# mpg-200-prototype_v3-with-logo.net
KiCad netlist of a schematic drawn in EAGLE
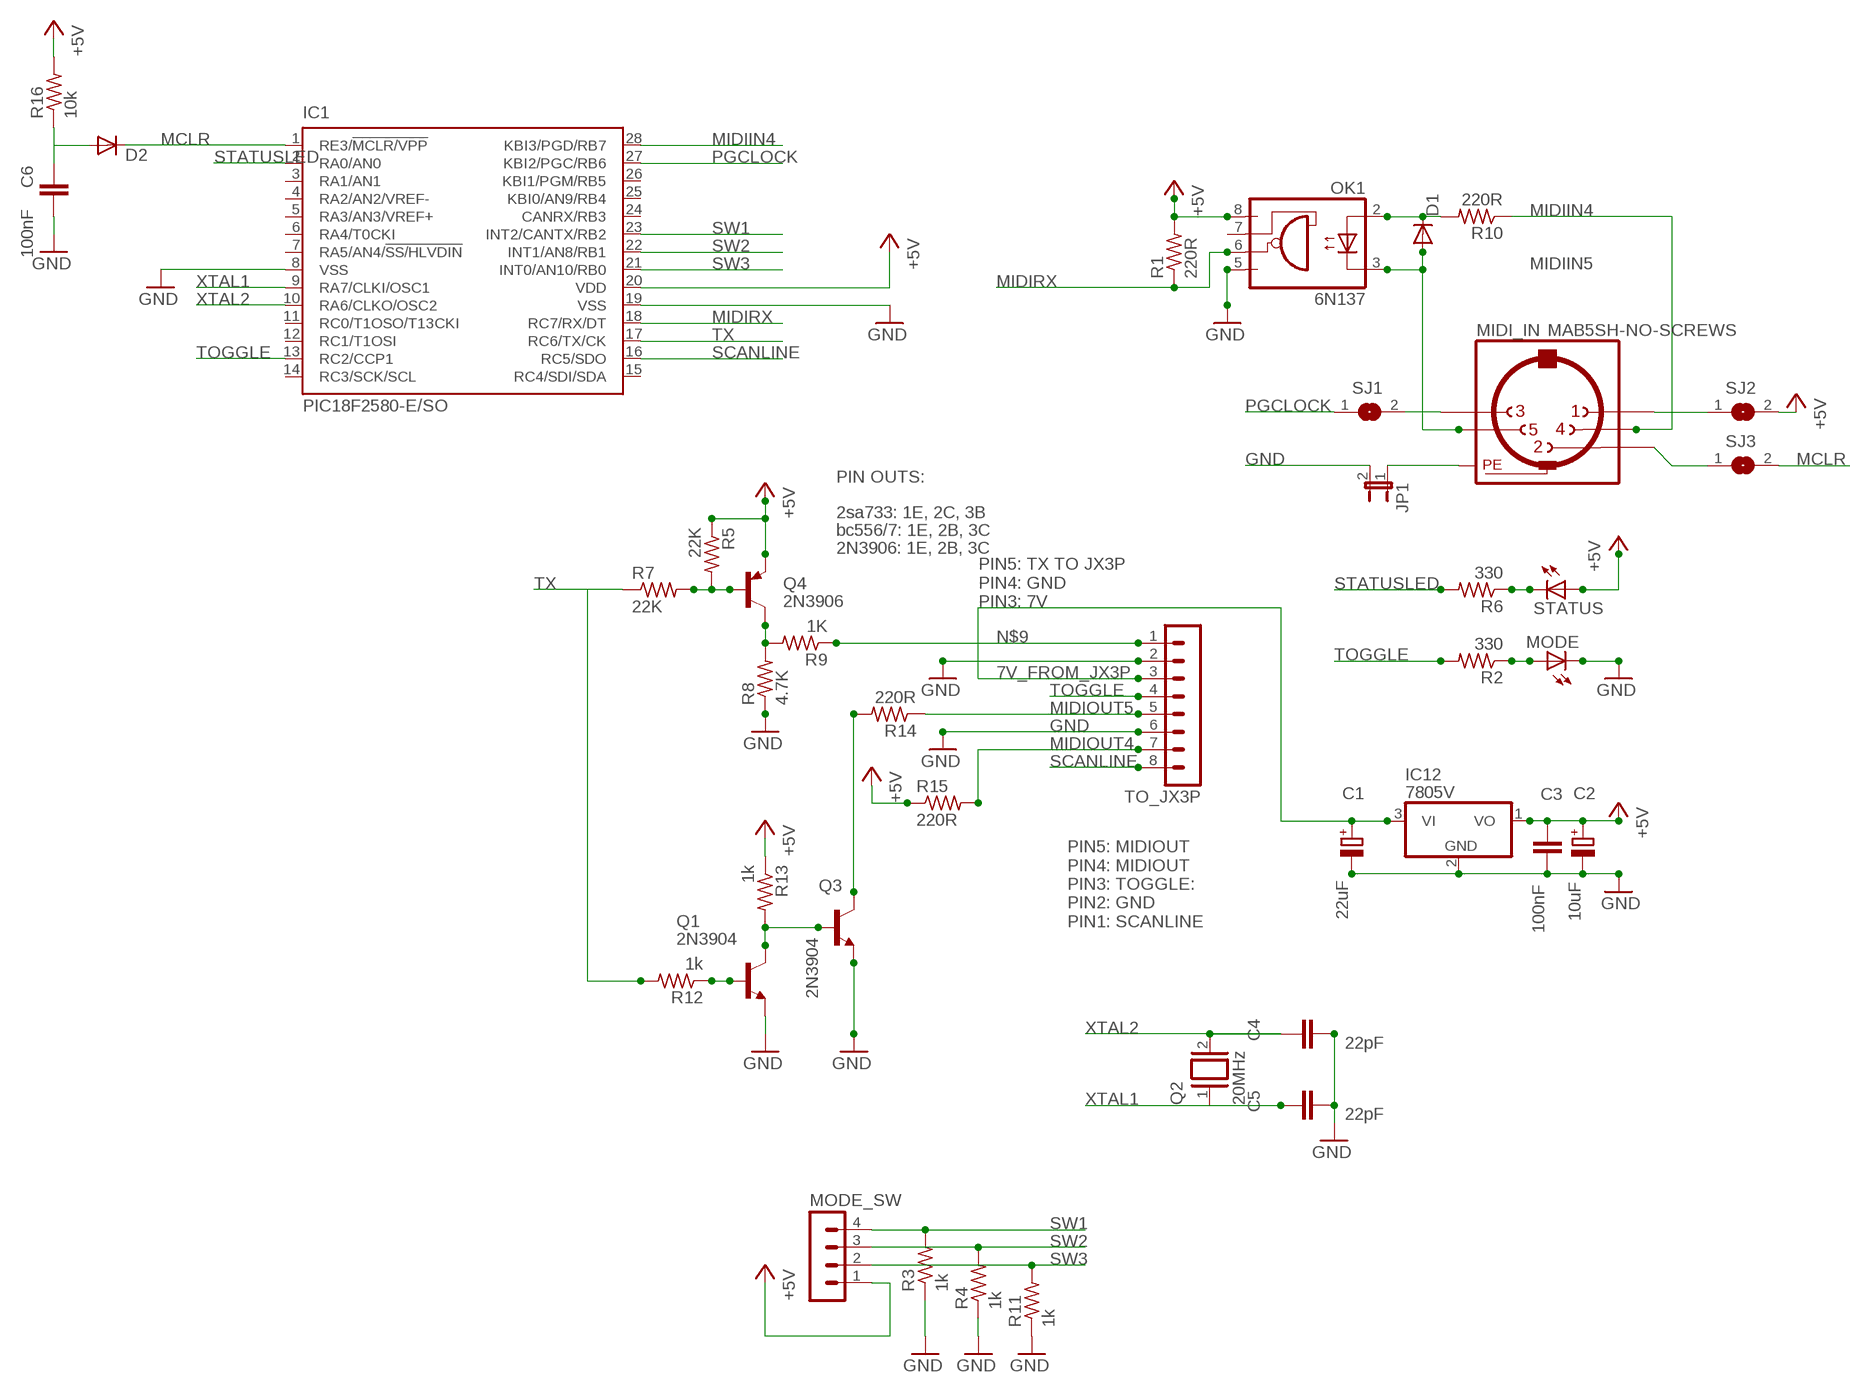
[diagram p0: schematic, sheet 1]

(export (version "E")
  (design (tool "Eeschema 10.0.6"))
  (components
    (comp (ref "C1")
      (value "22uF")
      (footprint "eagle-import:E2,5-5")
      (libsource (lib "eagle-import") (part "CPOL-EUE2.5-5"))
    )
    (comp (ref "C2")
      (value "10uF")
      (footprint "eagle-import:E2,5-5")
      (libsource (lib "eagle-import") (part "CPOL-EUE2.5-5"))
    )
    (comp (ref "C3")
      (value "100nF")
      (footprint "eagle-import:C0805")
      (libsource (lib "eagle-import") (part "C-EUC0805"))
    )
    (comp (ref "C4")
      (value "22pF")
      (footprint "eagle-import:C0805")
      (libsource (lib "eagle-import") (part "C-EUC0805"))
    )
    (comp (ref "C5")
      (value "22pF")
      (footprint "eagle-import:C0805")
      (libsource (lib "eagle-import") (part "C-EUC0805"))
    )
    (comp (ref "C6")
      (value "100nF")
      (footprint "eagle-import:C0805")
      (libsource (lib "eagle-import") (part "C-EUC0805"))
    )
    (comp (ref "D1")
      (value "DIODE-SOD80C")
      (footprint "eagle-import:SOD80C")
      (libsource (lib "eagle-import") (part "DIODE-SOD80C"))
    )
    (comp (ref "D2")
      (value "DIODE-SOD80C")
      (footprint "eagle-import:SOD80C")
      (libsource (lib "eagle-import") (part "DIODE-SOD80C"))
    )
    (comp (ref "IC1")
      (value "PIC18F2580-E/SO")
      (footprint "eagle-import:SO28W")
      (fields (field (name "MF") "MICROCHIP") (field (name "MPN") "PIC18F2580-I/SO"))
      (libsource (lib "eagle-import") (part "PIC18F280-E/SO5"))
    )
    (comp (ref "IC12")
      (value "7805V")
      (footprint "eagle-import:TO92")
      (libsource (lib "eagle-import") (part "78L05"))
    )
    (comp (ref "JP1")
      (value "JP1E")
      (footprint "eagle-import:JP1")
      (libsource (lib "eagle-import") (part "JP1E"))
    )
    (comp (ref "MIDI_IN")
      (value "MAB5SH-NO-SCREWS")
      (footprint "eagle-import:MAB5SH-NO-SCREWS")
      (libsource (lib "eagle-import") (part "MAB5SH-NO-SCREWS"))
    )
    (comp (ref "MODE")
      (value "LED3MM")
      (footprint "eagle-import:LED3MM")
      (libsource (lib "eagle-import") (part "LED3MM"))
    )
    (comp (ref "MODE_SW")
      (value "MA04-1")
      (footprint "eagle-import:MA04-1")
      (libsource (lib "eagle-import") (part "MA04-1"))
    )
    (comp (ref "OK1")
      (value "6N137")
      (footprint "eagle-import:DIL08")
      (libsource (lib "eagle-import") (part "6N137"))
    )
    (comp (ref "Q1")
      (value "2N3904")
      (footprint "eagle-import:TO92")
      (libsource (lib "eagle-import") (part "2N3904"))
    )
    (comp (ref "Q2")
      (value "20MHz")
      (footprint "eagle-import:QS")
      (libsource (lib "eagle-import") (part "XTAL/S"))
    )
    (comp (ref "Q3")
      (value "2N3904")
      (footprint "eagle-import:TO92")
      (libsource (lib "eagle-import") (part "2N3904"))
    )
    (comp (ref "Q4")
      (value "2N3906")
      (footprint "eagle-import:TO92")
      (libsource (lib "eagle-import") (part "2N3906"))
    )
    (comp (ref "R1")
      (value "220R")
      (footprint "eagle-import:R0805")
      (libsource (lib "eagle-import") (part "R-US_R0805"))
    )
    (comp (ref "R2")
      (value "330")
      (footprint "eagle-import:R0805")
      (libsource (lib "eagle-import") (part "R-US_R0805"))
    )
    (comp (ref "R3")
      (value "1k")
      (footprint "eagle-import:R0805")
      (libsource (lib "eagle-import") (part "R-US_R0805"))
    )
    (comp (ref "R4")
      (value "1k")
      (footprint "eagle-import:R0805")
      (libsource (lib "eagle-import") (part "R-US_R0805"))
    )
    (comp (ref "R5")
      (value "22K")
      (footprint "eagle-import:R0805")
      (libsource (lib "eagle-import") (part "R-US_R0805"))
    )
    (comp (ref "R6")
      (value "330")
      (footprint "eagle-import:R0805")
      (libsource (lib "eagle-import") (part "R-US_R0805"))
    )
    (comp (ref "R7")
      (value "22K")
      (footprint "eagle-import:R0805")
      (libsource (lib "eagle-import") (part "R-US_R0805"))
    )
    (comp (ref "R8")
      (value "4.7K")
      (footprint "eagle-import:R0805")
      (libsource (lib "eagle-import") (part "R-US_R0805"))
    )
    (comp (ref "R9")
      (value "1K")
      (footprint "eagle-import:R0805")
      (libsource (lib "eagle-import") (part "R-US_R0805"))
    )
    (comp (ref "R10")
      (value "220R")
      (footprint "eagle-import:R0805")
      (libsource (lib "eagle-import") (part "R-US_R0805"))
    )
    (comp (ref "R11")
      (value "1k")
      (footprint "eagle-import:R0805")
      (libsource (lib "eagle-import") (part "R-US_R0805"))
    )
    (comp (ref "R12")
      (value "1k")
      (footprint "eagle-import:R0805")
      (libsource (lib "eagle-import") (part "R-US_R0805"))
    )
    (comp (ref "R13")
      (value "1k")
      (footprint "eagle-import:R0805")
      (libsource (lib "eagle-import") (part "R-US_R0805"))
    )
    (comp (ref "R14")
      (value "220R")
      (footprint "eagle-import:R0805")
      (libsource (lib "eagle-import") (part "R-US_R0805"))
    )
    (comp (ref "R15")
      (value "220R")
      (footprint "eagle-import:R0805")
      (libsource (lib "eagle-import") (part "R-US_R0805"))
    )
    (comp (ref "R16")
      (value "10k")
      (footprint "eagle-import:R0805")
      (libsource (lib "eagle-import") (part "R-US_R0805"))
    )
    (comp (ref "SJ1") (value "SJ") (footprint "eagle-import:SJ") (libsource (lib "eagle-import") (part "SJ")))
    (comp (ref "SJ2") (value "SJ") (footprint "eagle-import:SJ") (libsource (lib "eagle-import") (part "SJ")))
    (comp (ref "SJ3") (value "SJ") (footprint "eagle-import:SJ") (libsource (lib "eagle-import") (part "SJ")))
    (comp (ref "STATUS")
      (value "LED3MM")
      (footprint "eagle-import:LED3MM")
      (libsource (lib "eagle-import") (part "LED3MM"))
    )
    (comp (ref "TO_JX3P")
      (value "MA08-1")
      (footprint "eagle-import:MA08-1")
      (libsource (lib "eagle-import") (part "MA08-1"))
    )
  )
  (nets
    (net (code "1") (name "+5V") (class "Default")
      (node (ref "C2") (pin "+") (pinfunction "+_+") (pintype "passive"))
      (node (ref "C3") (pin "1") (pinfunction "1_1") (pintype "passive"))
      (node (ref "IC1") (pin "20") (pinfunction "VDD_20") (pintype "power_in"))
      (node (ref "IC12") (pin "1") (pinfunction "VO_1") (pintype "passive"))
      (node (ref "MODE_SW") (pin "1") (pinfunction "1_1") (pintype "passive"))
      (node (ref "OK1") (pin "8") (pinfunction "VCC_8") (pintype "passive"))
      (node (ref "Q4") (pin "1") (pinfunction "E_1") (pintype "passive"))
      (node (ref "R1") (pin "2") (pinfunction "2_2") (pintype "passive"))
      (node (ref "R13") (pin "1") (pinfunction "1_1") (pintype "passive"))
      (node (ref "R15") (pin "1") (pinfunction "1_1") (pintype "passive"))
      (node (ref "R16") (pin "2") (pinfunction "2_2") (pintype "passive"))
      (node (ref "R5") (pin "1") (pinfunction "1_1") (pintype "passive"))
      (node (ref "SJ2") (pin "2") (pinfunction "2_2") (pintype "passive"))
      (node (ref "STATUS") (pin "A") (pinfunction "A_A") (pintype "passive"))
    )
    (net (code "2") (name "/7V_FROM_JX3P") (class "Default")
      (node (ref "C1") (pin "+") (pinfunction "+_+") (pintype "passive"))
      (node (ref "IC12") (pin "3") (pinfunction "VI_3") (pintype "input"))
      (node (ref "TO_JX3P") (pin "3") (pinfunction "3_3") (pintype "passive"))
    )
    (net (code "3") (name "/MCLR") (class "Default")
      (node (ref "D2") (pin "C") (pinfunction "C_C") (pintype "passive"))
      (node (ref "IC1") (pin "1") (pinfunction "RE3/~{MCLR/VPP}_1") (pintype "input"))
      (node (ref "SJ3") (pin "2") (pinfunction "2_2") (pintype "passive"))
    )
    (net (code "4") (name "/MIDIIN4") (class "Default")
      (node (ref "IC1") (pin "28") (pinfunction "KBI3/PGD/RB7_28") (pintype "bidirectional"))
      (node (ref "MIDI_IN") (pin "4") (pinfunction "4_4") (pintype "passive"))
      (node (ref "R10") (pin "1") (pinfunction "1_1") (pintype "passive"))
    )
    (net (code "5") (name "/MIDIIN5") (class "Default")
      (node (ref "D1") (pin "A") (pinfunction "A_A") (pintype "passive"))
      (node (ref "MIDI_IN") (pin "5") (pinfunction "5_5") (pintype "passive"))
      (node (ref "OK1") (pin "3") (pinfunction "C_3") (pintype "passive"))
    )
    (net (code "6") (name "/MIDIOUT4") (class "Default")
      (node (ref "R15") (pin "2") (pinfunction "2_2") (pintype "passive"))
      (node (ref "TO_JX3P") (pin "7") (pinfunction "7_7") (pintype "passive"))
    )
    (net (code "7") (name "/MIDIOUT5") (class "Default")
      (node (ref "R14") (pin "1") (pinfunction "1_1") (pintype "passive"))
      (node (ref "TO_JX3P") (pin "5") (pinfunction "5_5") (pintype "passive"))
    )
    (net (code "8") (name "/MIDIRX") (class "Default")
      (node (ref "IC1") (pin "18") (pinfunction "RC7/RX/DT_18") (pintype "bidirectional"))
      (node (ref "OK1") (pin "6") (pinfunction "VO_6") (pintype "passive"))
      (node (ref "R1") (pin "1") (pinfunction "1_1") (pintype "passive"))
    )
    (net (code "9") (name "/N$9") (class "Default")
      (node (ref "R9") (pin "1") (pinfunction "1_1") (pintype "passive"))
      (node (ref "TO_JX3P") (pin "1") (pinfunction "1_1") (pintype "passive"))
    )
    (net (code "10") (name "/PGCLOCK") (class "Default")
      (node (ref "IC1") (pin "27") (pinfunction "KBI2/PGC/RB6_27") (pintype "bidirectional"))
      (node (ref "SJ1") (pin "1") (pinfunction "1_1") (pintype "passive"))
    )
    (net (code "11") (name "/SCANLINE") (class "Default")
      (node (ref "IC1") (pin "16") (pinfunction "RC5/SDO_16") (pintype "bidirectional"))
      (node (ref "TO_JX3P") (pin "8") (pinfunction "8_8") (pintype "passive"))
    )
    (net (code "12") (name "/STATUSLED") (class "Default")
      (node (ref "IC1") (pin "2") (pinfunction "RA0/AN0_2") (pintype "bidirectional"))
      (node (ref "R6") (pin "2") (pinfunction "2_2") (pintype "passive"))
    )
    (net (code "13") (name "/SW1") (class "Default")
      (node (ref "IC1") (pin "23") (pinfunction "INT2/CANTX/RB2_23") (pintype "bidirectional"))
      (node (ref "MODE_SW") (pin "4") (pinfunction "4_4") (pintype "passive"))
      (node (ref "R3") (pin "2") (pinfunction "2_2") (pintype "passive"))
    )
    (net (code "14") (name "/SW2") (class "Default")
      (node (ref "IC1") (pin "22") (pinfunction "INT1/AN8/RB1_22") (pintype "bidirectional"))
      (node (ref "MODE_SW") (pin "3") (pinfunction "3_3") (pintype "passive"))
      (node (ref "R4") (pin "2") (pinfunction "2_2") (pintype "passive"))
    )
    (net (code "15") (name "/SW3") (class "Default")
      (node (ref "IC1") (pin "21") (pinfunction "INT0/AN10/RB0_21") (pintype "bidirectional"))
      (node (ref "MODE_SW") (pin "2") (pinfunction "2_2") (pintype "passive"))
      (node (ref "R11") (pin "2") (pinfunction "2_2") (pintype "passive"))
    )
    (net (code "16") (name "/TOGGLE") (class "Default")
      (node (ref "IC1") (pin "13") (pinfunction "RC2/CCP1_13") (pintype "bidirectional"))
      (node (ref "R2") (pin "2") (pinfunction "2_2") (pintype "passive"))
      (node (ref "TO_JX3P") (pin "4") (pinfunction "4_4") (pintype "passive"))
    )
    (net (code "17") (name "/TX") (class "Default")
      (node (ref "IC1") (pin "17") (pinfunction "RC6/TX/CK_17") (pintype "bidirectional"))
      (node (ref "R12") (pin "2") (pinfunction "2_2") (pintype "passive"))
      (node (ref "R7") (pin "1") (pinfunction "1_1") (pintype "passive"))
    )
    (net (code "18") (name "/XTAL1") (class "Default")
      (node (ref "C5") (pin "1") (pinfunction "1_1") (pintype "passive"))
      (node (ref "IC1") (pin "9") (pinfunction "RA7/CLKI/OSC1_9") (pintype "input"))
      (node (ref "Q2") (pin "1") (pinfunction "1_1") (pintype "passive"))
    )
    (net (code "19") (name "/XTAL2") (class "Default")
      (node (ref "C4") (pin "1") (pinfunction "1_1") (pintype "passive"))
      (node (ref "IC1") (pin "10") (pinfunction "RA6/CLKO/OSC2_10") (pintype "output"))
      (node (ref "Q2") (pin "2") (pinfunction "2_2") (pintype "passive"))
    )
    (net (code "20") (name "GND") (class "Default")
      (node (ref "C1") (pin "-") (pinfunction "-_-") (pintype "passive"))
      (node (ref "C2") (pin "-") (pinfunction "-_-") (pintype "passive"))
      (node (ref "C3") (pin "2") (pinfunction "2_2") (pintype "passive"))
      (node (ref "C4") (pin "2") (pinfunction "2_2") (pintype "passive"))
      (node (ref "C5") (pin "2") (pinfunction "2_2") (pintype "passive"))
      (node (ref "C6") (pin "2") (pinfunction "2_2") (pintype "passive"))
      (node (ref "IC1") (pin "19") (pinfunction "VSS_19") (pintype "power_in"))
      (node (ref "IC1") (pin "8") (pinfunction "VSS_8") (pintype "power_in"))
      (node (ref "IC12") (pin "2") (pinfunction "GND_2") (pintype "passive"))
      (node (ref "JP1") (pin "2") (pinfunction "2_2") (pintype "passive"))
      (node (ref "MODE") (pin "K") (pinfunction "C_K") (pintype "passive"))
      (node (ref "OK1") (pin "5") (pinfunction "GND_5") (pintype "passive"))
      (node (ref "Q1") (pin "1") (pinfunction "E_1") (pintype "passive"))
      (node (ref "Q3") (pin "1") (pinfunction "E_1") (pintype "passive"))
      (node (ref "R11") (pin "1") (pinfunction "1_1") (pintype "passive"))
      (node (ref "R3") (pin "1") (pinfunction "1_1") (pintype "passive"))
      (node (ref "R4") (pin "1") (pinfunction "1_1") (pintype "passive"))
      (node (ref "R8") (pin "1") (pinfunction "1_1") (pintype "passive"))
      (node (ref "TO_JX3P") (pin "2") (pinfunction "2_2") (pintype "passive"))
      (node (ref "TO_JX3P") (pin "6") (pinfunction "6_6") (pintype "passive"))
    )
    (net (code "21") (name "Net-(C6-Pad1)") (class "Default")
      (node (ref "C6") (pin "1") (pinfunction "1_1") (pintype "passive"))
      (node (ref "D2") (pin "A") (pinfunction "A_A") (pintype "passive"))
      (node (ref "R16") (pin "1") (pinfunction "1_1") (pintype "passive"))
    )
    (net (code "22") (name "Net-(JP1-Pad1)") (class "Default")
      (node (ref "JP1") (pin "1") (pinfunction "1_1") (pintype "passive"))
      (node (ref "MIDI_IN") (pin "PE") (pinfunction "PE_PE") (pintype "power_in"))
      (node (ref "MIDI_IN") (pin "PE@") (pinfunction "PE_PE@") (pintype "power_in"))
    )
    (net (code "23") (name "Net-(MIDI_IN-Pad1)") (class "Default")
      (node (ref "MIDI_IN") (pin "1") (pinfunction "1_1") (pintype "passive"))
      (node (ref "SJ2") (pin "1") (pinfunction "1_1") (pintype "passive"))
    )
    (net (code "24") (name "Net-(MIDI_IN-Pad2)") (class "Default")
      (node (ref "MIDI_IN") (pin "2") (pinfunction "2_2") (pintype "passive"))
      (node (ref "SJ3") (pin "1") (pinfunction "1_1") (pintype "passive"))
    )
    (net (code "25") (name "Net-(MIDI_IN-Pad3)") (class "Default")
      (node (ref "MIDI_IN") (pin "3") (pinfunction "3_3") (pintype "passive"))
      (node (ref "SJ1") (pin "2") (pinfunction "2_2") (pintype "passive"))
    )
    (net (code "26") (name "Net-(MODE-PadA)") (class "Default")
      (node (ref "MODE") (pin "A") (pinfunction "A_A") (pintype "passive"))
      (node (ref "R2") (pin "1") (pinfunction "1_1") (pintype "passive"))
    )
    (net (code "27") (name "Net-(OK1-A)") (class "Default")
      (node (ref "D1") (pin "C") (pinfunction "C_C") (pintype "passive"))
      (node (ref "OK1") (pin "2") (pinfunction "A_2") (pintype "passive"))
      (node (ref "R10") (pin "2") (pinfunction "2_2") (pintype "passive"))
    )
    (net (code "28") (name "Net-(Q1-B)") (class "Default")
      (node (ref "Q1") (pin "2") (pinfunction "B_2") (pintype "passive"))
      (node (ref "R12") (pin "1") (pinfunction "1_1") (pintype "passive"))
    )
    (net (code "29") (name "Net-(Q1-C)") (class "Default")
      (node (ref "Q1") (pin "3") (pinfunction "C_3") (pintype "passive"))
      (node (ref "Q3") (pin "2") (pinfunction "B_2") (pintype "passive"))
      (node (ref "R13") (pin "2") (pinfunction "2_2") (pintype "passive"))
    )
    (net (code "30") (name "Net-(Q3-C)") (class "Default")
      (node (ref "Q3") (pin "3") (pinfunction "C_3") (pintype "passive"))
      (node (ref "R14") (pin "2") (pinfunction "2_2") (pintype "passive"))
    )
    (net (code "31") (name "Net-(Q4-B)") (class "Default")
      (node (ref "Q4") (pin "2") (pinfunction "B_2") (pintype "passive"))
      (node (ref "R5") (pin "2") (pinfunction "2_2") (pintype "passive"))
      (node (ref "R7") (pin "2") (pinfunction "2_2") (pintype "passive"))
    )
    (net (code "32") (name "Net-(Q4-C)") (class "Default")
      (node (ref "Q4") (pin "3") (pinfunction "C_3") (pintype "passive"))
      (node (ref "R8") (pin "2") (pinfunction "2_2") (pintype "passive"))
      (node (ref "R9") (pin "2") (pinfunction "2_2") (pintype "passive"))
    )
    (net (code "33") (name "Net-(STATUS-C)") (class "Default")
      (node (ref "R6") (pin "1") (pinfunction "1_1") (pintype "passive"))
      (node (ref "STATUS") (pin "K") (pinfunction "C_K") (pintype "passive"))
    )
    (net (code "34") (name "unconnected-(IC1-CANRX{slash}RB3-Pad24)") (class "Default")
      (node (ref "IC1") (pin "24") (pinfunction "CANRX/RB3_24") (pintype "bidirectional"))
    )
    (net (code "35") (name "unconnected-(IC1-KBI0{slash}AN9{slash}RB4-Pad25)") (class "Default")
      (node (ref "IC1") (pin "25") (pinfunction "KBI0/AN9/RB4_25") (pintype "bidirectional"))
    )
    (net (code "36") (name "unconnected-(IC1-KBI1{slash}PGM{slash}RB5-Pad26)") (class "Default")
      (node (ref "IC1") (pin "26") (pinfunction "KBI1/PGM/RB5_26") (pintype "bidirectional"))
    )
    (net (code "37") (name "unconnected-(IC1-RA1{slash}AN1-Pad3)") (class "Default")
      (node (ref "IC1") (pin "3") (pinfunction "RA1/AN1_3") (pintype "bidirectional"))
    )
    (net (code "38") (name "unconnected-(IC1-RA2{slash}AN2{slash}VREF--Pad4)") (class "Default")
      (node (ref "IC1") (pin "4") (pinfunction "RA2/AN2/VREF-_4") (pintype "bidirectional"))
    )
    (net (code "39") (name "unconnected-(IC1-RA3{slash}AN3{slash}VREF+-Pad5)") (class "Default")
      (node (ref "IC1") (pin "5") (pinfunction "RA3/AN3/VREF+_5") (pintype "bidirectional"))
    )
    (net (code "40") (name "unconnected-(IC1-RA4{slash}T0CKI-Pad6)") (class "Default")
      (node (ref "IC1") (pin "6") (pinfunction "RA4/T0CKI_6") (pintype "bidirectional"))
    )
    (net (code "41") (name "unconnected-(IC1-RA5{slash}AN4{slash}~{SS{slash}HLVDIN}-Pad7)") (class "Default")
      (node (ref "IC1") (pin "7") (pinfunction "RA5/AN4/~{SS/HLVDIN}_7") (pintype "bidirectional"))
    )
    (net (code "42") (name "unconnected-(IC1-RC0{slash}T1OSO{slash}T13CKI-Pad11)") (class "Default")
      (node (ref "IC1") (pin "11") (pinfunction "RC0/T1OSO/T13CKI_11") (pintype "bidirectional"))
    )
    (net (code "43") (name "unconnected-(IC1-RC1{slash}T1OSI-Pad12)") (class "Default")
      (node (ref "IC1") (pin "12") (pinfunction "RC1/T1OSI_12") (pintype "bidirectional"))
    )
    (net (code "44") (name "unconnected-(IC1-RC3{slash}SCK{slash}SCL-Pad14)") (class "Default")
      (node (ref "IC1") (pin "14") (pinfunction "RC3/SCK/SCL_14") (pintype "bidirectional"))
    )
    (net (code "45") (name "unconnected-(IC1-RC4{slash}SDI{slash}SDA-Pad15)") (class "Default")
      (node (ref "IC1") (pin "15") (pinfunction "RC4/SDI/SDA_15") (pintype "bidirectional"))
    )
    (net (code "46") (name "unconnected-(OK1-VE-Pad7)") (class "Default")
      (node (ref "OK1") (pin "7") (pinfunction "VE_7") (pintype "passive"))
    )
  )
)
